# HeatSink.net
KiCad netlist of a schematic drawn in Altium Designer
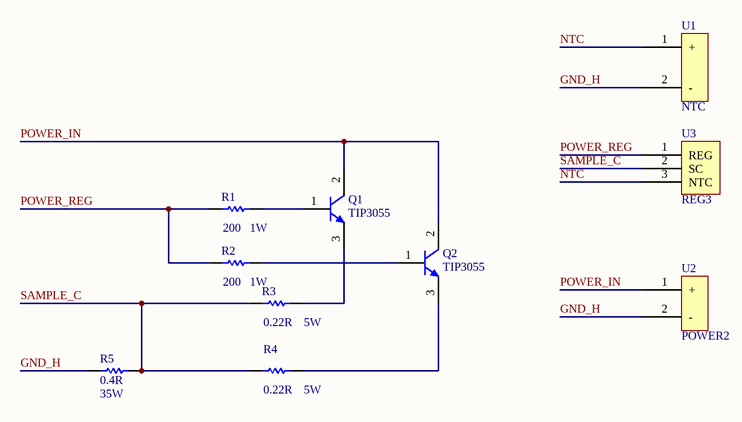
[diagram p0: HeatSink.SchDoc]

(export (version "E")
  (design (tool "Eeschema 10.0.6"))
  (components
    (comp (ref "Q1")
      (value "TIP3055")
      (footprint "CNCPowerSupply:TO-247-ZUO")
      (description "NPN Bipolar Transistor")
      (fields (field (name "PUBLISHER") "Altium Limited"))
      (libsource (lib "Miscellaneous Devices") (part "NPN"))
    )
    (comp (ref "Q2")
      (value "TIP3055")
      (footprint "CNCPowerSupply:TO-247-ZUO")
      (description "NPN Bipolar Transistor")
      (fields (field (name "PUBLISHER") "Altium Limited"))
      (libsource (lib "Miscellaneous Devices") (part "NPN"))
    )
    (comp (ref "R1")
      (value "1W")
      (footprint "CNCPowerSupply:AXIAL-0.7")
      (description "Resistor")
      (fields (field (name "ALTIUM_VALUE") "200") (field (name "PUBLISHER") "Altium Limited"))
      (libsource (lib "Miscellaneous Devices") (part "Res1"))
    )
    (comp (ref "R2")
      (value "1W")
      (footprint "CNCPowerSupply:AXIAL-0.7")
      (description "Resistor")
      (fields (field (name "ALTIUM_VALUE") "200") (field (name "PUBLISHER") "Altium Limited"))
      (libsource (lib "Miscellaneous Devices") (part "Res1"))
    )
    (comp (ref "R3")
      (value "5W")
      (footprint "CNCPowerSupply:AXIAL-0.4-BigHole")
      (description "Resistor")
      (fields (field (name "ALTIUM_VALUE") "0.22R") (field (name "PUBLISHER") "Altium Limited"))
      (libsource (lib "Miscellaneous Devices") (part "Res1"))
    )
    (comp (ref "R4")
      (value "5W")
      (footprint "CNCPowerSupply:AXIAL-0.4-BigHole")
      (description "Resistor")
      (fields (field (name "ALTIUM_VALUE") "0.22R") (field (name "PUBLISHER") "Altium Limited"))
      (libsource (lib "Miscellaneous Devices") (part "Res1"))
    )
    (comp (ref "R5")
      (value "35W")
      (footprint "CNCPowerSupply:TO-220AB - 2 Legs")
      (description "Resistor")
      (fields (field (name "ALTIUM_VALUE") "0.4R") (field (name "PUBLISHER") "Altium Limited"))
      (libsource (lib "Miscellaneous Devices") (part "Res1"))
    )
    (comp (ref "U1")
      (value "NTC")
      (footprint "CNCPowerSupply:X254-2P")
      (libsource (lib "CNCPowerSupply") (part "NTC"))
    )
    (comp (ref "U2")
      (value "POWER2")
      (footprint "CNCPowerSupply:KF128-50-2P")
      (libsource (lib "CNCPowerSupply") (part "POWER2"))
    )
    (comp (ref "U3")
      (value "REG3")
      (footprint "CNCPowerSupply:X254-3P")
      (description "REG2")
      (libsource (lib "CNCPowerSupply") (part "REG3"))
    )
  )
  (nets
    (net (code "1") (name "/GND_H") (class "Default")
      (node (ref "R5") (pin "2") (pinfunction "2_2") (pintype "passive"))
      (node (ref "U1") (pin "2") (pinfunction "-_2") (pintype "passive"))
      (node (ref "U2") (pin "2") (pinfunction "-_2") (pintype "passive"))
    )
    (net (code "2") (name "/NTC") (class "Default")
      (node (ref "U1") (pin "1") (pinfunction "+_1") (pintype "passive"))
      (node (ref "U3") (pin "3") (pinfunction "NTC_3") (pintype "passive"))
    )
    (net (code "3") (name "/POWER_IN") (class "Default")
      (node (ref "Q1") (pin "2") (pinfunction "C_2") (pintype "passive"))
      (node (ref "Q2") (pin "2") (pinfunction "C_2") (pintype "passive"))
      (node (ref "U2") (pin "1") (pinfunction "+_1") (pintype "passive"))
    )
    (net (code "4") (name "/POWER_REG") (class "Default")
      (node (ref "R1") (pin "2") (pinfunction "2_2") (pintype "passive"))
      (node (ref "R2") (pin "2") (pinfunction "2_2") (pintype "passive"))
      (node (ref "U3") (pin "1") (pinfunction "REG_1") (pintype "passive"))
    )
    (net (code "5") (name "/SAMPLE_C") (class "Default")
      (node (ref "R3") (pin "2") (pinfunction "2_2") (pintype "passive"))
      (node (ref "R4") (pin "2") (pinfunction "2_2") (pintype "passive"))
      (node (ref "R5") (pin "1") (pinfunction "1_1") (pintype "passive"))
      (node (ref "U3") (pin "2") (pinfunction "SC_2") (pintype "passive"))
    )
    (net (code "6") (name "Net-(Q1-B)") (class "Default")
      (node (ref "Q1") (pin "1") (pinfunction "B_1") (pintype "passive"))
      (node (ref "R1") (pin "1") (pinfunction "1_1") (pintype "passive"))
    )
    (net (code "7") (name "Net-(Q1-E)") (class "Default")
      (node (ref "Q1") (pin "3") (pinfunction "E_3") (pintype "passive"))
      (node (ref "R3") (pin "1") (pinfunction "1_1") (pintype "passive"))
    )
    (net (code "8") (name "Net-(Q2-B)") (class "Default")
      (node (ref "Q2") (pin "1") (pinfunction "B_1") (pintype "passive"))
      (node (ref "R2") (pin "1") (pinfunction "1_1") (pintype "passive"))
    )
    (net (code "9") (name "Net-(Q2-E)") (class "Default")
      (node (ref "Q2") (pin "3") (pinfunction "E_3") (pintype "passive"))
      (node (ref "R4") (pin "1") (pinfunction "1_1") (pintype "passive"))
    )
  )
)
